# amp_soha_v3.net
KiCad netlist of a schematic drawn in EAGLE
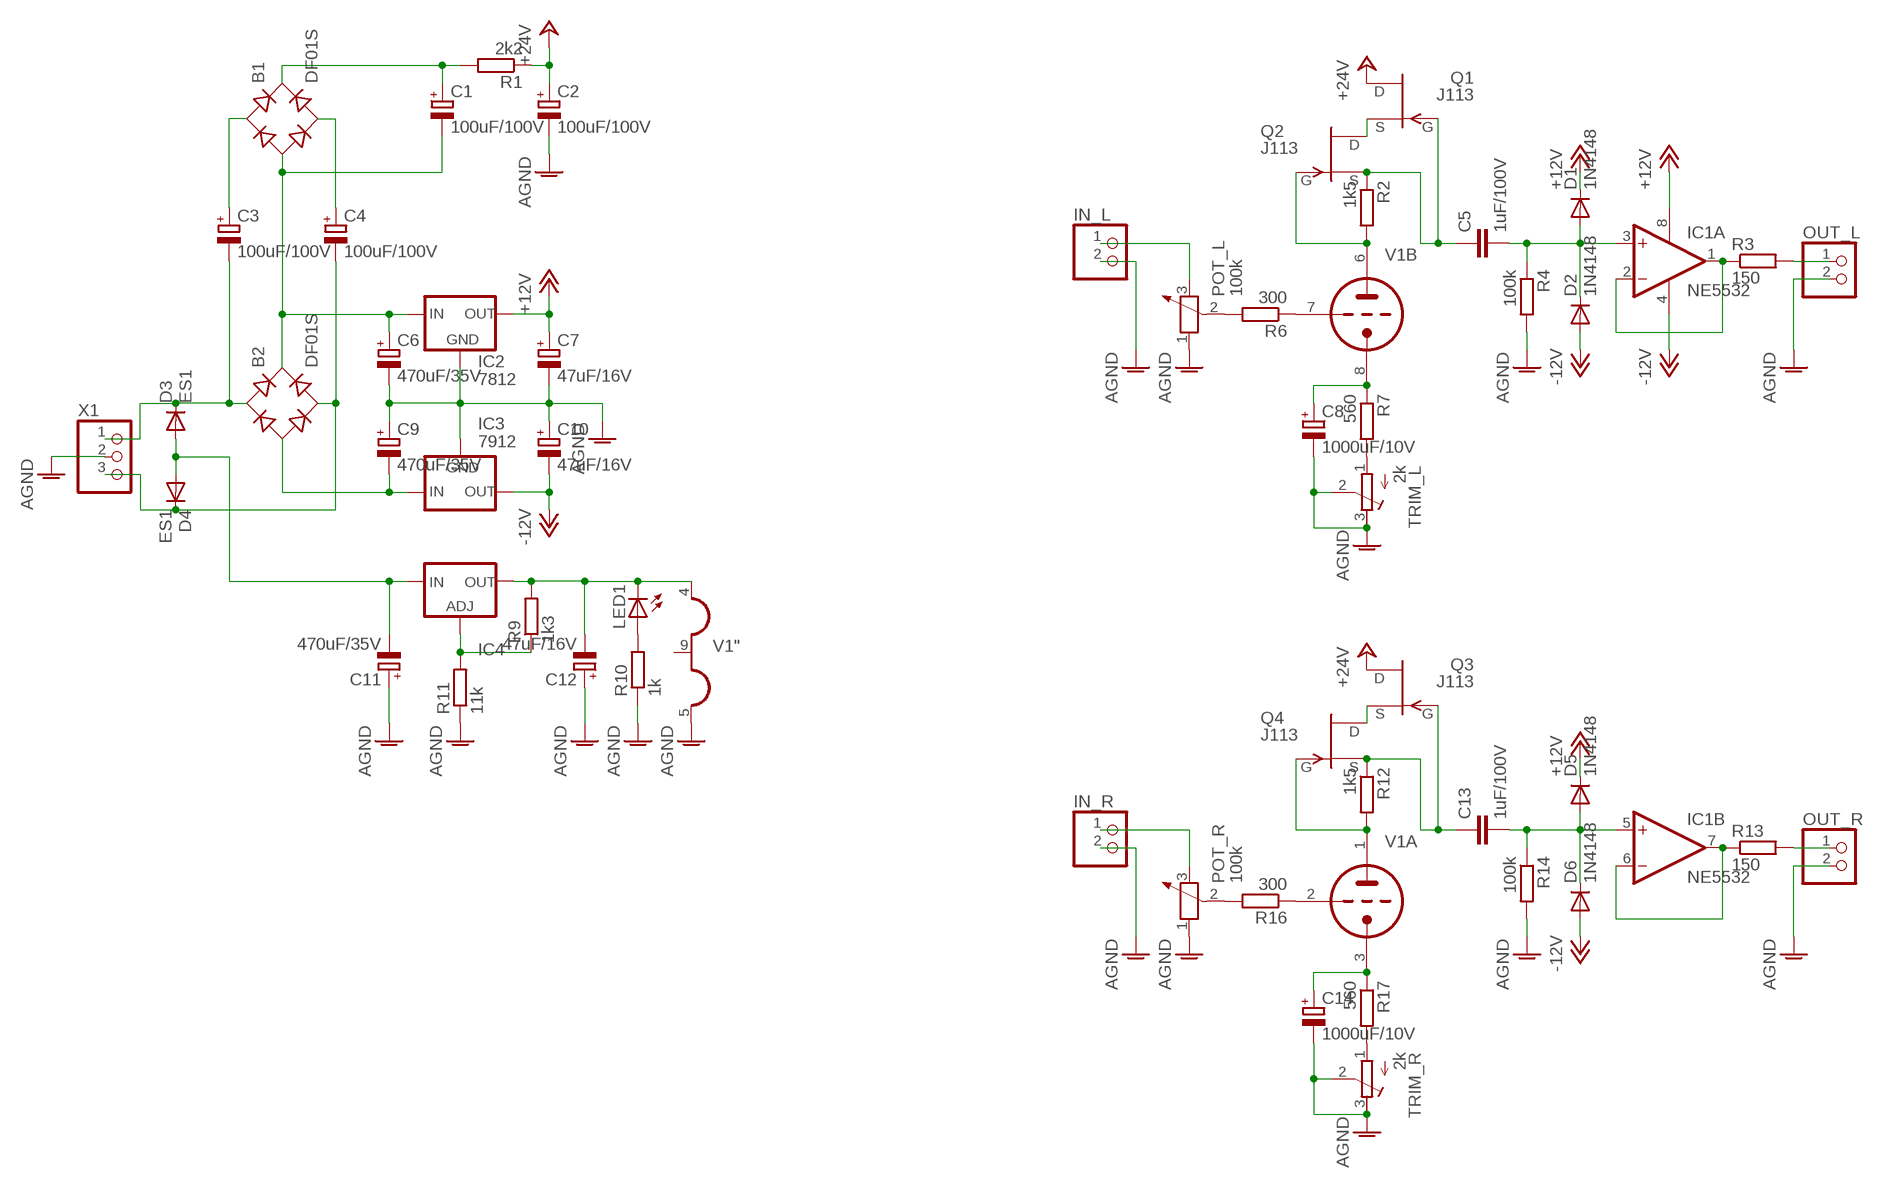
[diagram p0: schematic, sheet 1]

(export (version "E")
  (design (tool "Eeschema 10.0.6"))
  (components
    (comp (ref "B1")
      (value "DF01S")
      (footprint "eagle-import:DFS")
      (libsource (lib "eagle-import") (part "DFS01"))
    )
    (comp (ref "B2")
      (value "DF01S")
      (footprint "eagle-import:DFS")
      (libsource (lib "eagle-import") (part "DFS01"))
    )
    (comp (ref "C1")
      (value "100uF/100V")
      (footprint "eagle-import:E5-10,5")
      (libsource (lib "eagle-import") (part "CPOL-EUE5-10,5"))
    )
    (comp (ref "C2")
      (value "100uF/100V")
      (footprint "eagle-import:E5-10,5")
      (libsource (lib "eagle-import") (part "CPOL-EUE5-10,5"))
    )
    (comp (ref "C3")
      (value "100uF/100V")
      (footprint "eagle-import:E5-10,5")
      (libsource (lib "eagle-import") (part "CPOL-EUE5-10,5"))
    )
    (comp (ref "C4")
      (value "100uF/100V")
      (footprint "eagle-import:E5-10,5")
      (libsource (lib "eagle-import") (part "CPOL-EUE5-10,5"))
    )
    (comp (ref "C5")
      (value "1uF/100V")
      (footprint "eagle-import:C075-052X106")
      (libsource (lib "eagle-import") (part "C-EU075-052X106"))
    )
    (comp (ref "C6")
      (value "470uF/35V")
      (footprint "eagle-import:E5-10,5")
      (libsource (lib "eagle-import") (part "CPOL-EUE5-10,5"))
    )
    (comp (ref "C7")
      (value "47uF/16V")
      (footprint "eagle-import:E2,5-6")
      (libsource (lib "eagle-import") (part "CPOL-EUE2.5-6"))
    )
    (comp (ref "C8")
      (value "1000uF/10V")
      (footprint "eagle-import:E5-10,5")
      (libsource (lib "eagle-import") (part "CPOL-EUE5-10,5"))
    )
    (comp (ref "C9")
      (value "470uF/35V")
      (footprint "eagle-import:E5-10,5")
      (libsource (lib "eagle-import") (part "CPOL-EUE5-10,5"))
    )
    (comp (ref "C10")
      (value "47uF/16V")
      (footprint "eagle-import:E2,5-6")
      (libsource (lib "eagle-import") (part "CPOL-EUE2.5-6"))
    )
    (comp (ref "C11")
      (value "470uF/35V")
      (footprint "eagle-import:E5-10,5")
      (libsource (lib "eagle-import") (part "CPOL-EUE5-10,5"))
    )
    (comp (ref "C12")
      (value "47uF/16V")
      (footprint "eagle-import:E2,5-6")
      (libsource (lib "eagle-import") (part "CPOL-EUE2.5-6"))
    )
    (comp (ref "C13")
      (value "1uF/100V")
      (footprint "eagle-import:C075-052X106")
      (libsource (lib "eagle-import") (part "C-EU075-052X106"))
    )
    (comp (ref "C14")
      (value "1000uF/10V")
      (footprint "eagle-import:E5-10,5")
      (libsource (lib "eagle-import") (part "CPOL-EUE5-10,5"))
    )
    (comp (ref "D1")
      (value "1N4148")
      (footprint "eagle-import:D0805")
      (libsource (lib "eagle-import") (part "1N4148"))
    )
    (comp (ref "D2")
      (value "1N4148")
      (footprint "eagle-import:D0805")
      (libsource (lib "eagle-import") (part "1N4148"))
    )
    (comp (ref "D3")
      (value "ES1")
      (footprint "eagle-import:DO-214AC")
      (libsource (lib "eagle-import") (part "ES1"))
    )
    (comp (ref "D4")
      (value "ES1")
      (footprint "eagle-import:DO-214AC")
      (libsource (lib "eagle-import") (part "ES1"))
    )
    (comp (ref "D5")
      (value "1N4148")
      (footprint "eagle-import:D0805")
      (libsource (lib "eagle-import") (part "1N4148"))
    )
    (comp (ref "D6")
      (value "1N4148")
      (footprint "eagle-import:D0805")
      (libsource (lib "eagle-import") (part "1N4148"))
    )
    (comp (ref "IC1")
      (value "NE5532")
      (footprint "eagle-import:SO08")
      (libsource (lib "eagle-import") (part "NE5535U"))
    )
    (comp (ref "IC2")
      (value "7812")
      (footprint "eagle-import:78XXS")
      (libsource (lib "eagle-import") (part "78XXTO-220"))
    )
    (comp (ref "IC3")
      (value "7912")
      (footprint "eagle-import:79XXS")
      (libsource (lib "eagle-import") (part "79XXTO-220"))
    )
    (comp (ref "IC4")
      (value "LM337TS")
      (footprint "eagle-import:337TS")
      (libsource (lib "eagle-import") (part "LM337TS"))
    )
    (comp (ref "IN_L")
      (value "PINHD-1X2")
      (footprint "eagle-import:1X02")
      (libsource (lib "eagle-import") (part "PINHD-1X2"))
    )
    (comp (ref "IN_R")
      (value "PINHD-1X2")
      (footprint "eagle-import:1X02")
      (libsource (lib "eagle-import") (part "PINHD-1X2"))
    )
    (comp (ref "LED1")
      (value "LED5MM")
      (footprint "eagle-import:LED5MM")
      (libsource (lib "eagle-import") (part "LED5MM"))
    )
    (comp (ref "OUT_L")
      (value "PINHD-1X2")
      (footprint "eagle-import:1X02")
      (libsource (lib "eagle-import") (part "PINHD-1X2"))
    )
    (comp (ref "OUT_R")
      (value "PINHD-1X2")
      (footprint "eagle-import:1X02")
      (libsource (lib "eagle-import") (part "PINHD-1X2"))
    )
    (comp (ref "POT_L")
      (value "100k")
      (footprint "eagle-import:1X03")
      (libsource (lib "eagle-import") (part "POTENTIOMETER_"))
    )
    (comp (ref "POT_R")
      (value "100k")
      (footprint "eagle-import:1X03")
      (libsource (lib "eagle-import") (part "POTENTIOMETER_"))
    )
    (comp (ref "Q1")
      (value "J113")
      (footprint "eagle-import:TO92")
      (libsource (lib "eagle-import") (part "J113"))
    )
    (comp (ref "Q2")
      (value "J113")
      (footprint "eagle-import:TO92")
      (libsource (lib "eagle-import") (part "J113"))
    )
    (comp (ref "Q3")
      (value "J113")
      (footprint "eagle-import:TO92")
      (libsource (lib "eagle-import") (part "J113"))
    )
    (comp (ref "Q4")
      (value "J113")
      (footprint "eagle-import:TO92")
      (libsource (lib "eagle-import") (part "J113"))
    )
    (comp (ref "R1")
      (value "2k2")
      (footprint "eagle-import:R0805")
      (libsource (lib "eagle-import") (part "R-EU_"))
    )
    (comp (ref "R2")
      (value "1k5")
      (footprint "eagle-import:R0805")
      (libsource (lib "eagle-import") (part "R-EU_"))
    )
    (comp (ref "R3")
      (value "150")
      (footprint "eagle-import:R0805")
      (libsource (lib "eagle-import") (part "R-EU_"))
    )
    (comp (ref "R4")
      (value "100k")
      (footprint "eagle-import:R0805")
      (libsource (lib "eagle-import") (part "R-EU_"))
    )
    (comp (ref "R6")
      (value "300")
      (footprint "eagle-import:R0805")
      (libsource (lib "eagle-import") (part "R-EU_"))
    )
    (comp (ref "R7")
      (value "560")
      (footprint "eagle-import:R0805")
      (libsource (lib "eagle-import") (part "R-EU_"))
    )
    (comp (ref "R9")
      (value "1k3")
      (footprint "eagle-import:R0805")
      (libsource (lib "eagle-import") (part "R-EU_"))
    )
    (comp (ref "R10")
      (value "1k")
      (footprint "eagle-import:R0805")
      (libsource (lib "eagle-import") (part "R-EU_"))
    )
    (comp (ref "R11")
      (value "11k")
      (footprint "eagle-import:R0805")
      (libsource (lib "eagle-import") (part "R-EU_"))
    )
    (comp (ref "R12")
      (value "1k5")
      (footprint "eagle-import:R0805")
      (libsource (lib "eagle-import") (part "R-EU_"))
    )
    (comp (ref "R13")
      (value "150")
      (footprint "eagle-import:R0805")
      (libsource (lib "eagle-import") (part "R-EU_"))
    )
    (comp (ref "R14")
      (value "100k")
      (footprint "eagle-import:R0805")
      (libsource (lib "eagle-import") (part "R-EU_"))
    )
    (comp (ref "R16")
      (value "300")
      (footprint "eagle-import:R0805")
      (libsource (lib "eagle-import") (part "R-EU_"))
    )
    (comp (ref "R17")
      (value "560")
      (footprint "eagle-import:R0805")
      (libsource (lib "eagle-import") (part "R-EU_"))
    )
    (comp (ref "TRIM_L")
      (value "2k")
      (footprint "eagle-import:RTRIM3296W")
      (libsource (lib "eagle-import") (part "RTRIM329W"))
    )
    (comp (ref "TRIM_R")
      (value "2k")
      (footprint "eagle-import:RTRIM3296W")
      (libsource (lib "eagle-import") (part "RTRIM329W"))
    )
    (comp (ref "V1")
      (value "12AU7-P")
      (footprint "eagle-import:NOVAL")
      (libsource (lib "eagle-import") (part "12AU7-P"))
    )
    (comp (ref "X1")
      (value "W237-103")
      (footprint "eagle-import:W237-103")
      (libsource (lib "eagle-import") (part "W237-103"))
    )
  )
  (nets
    (net (code "1") (name "+12V") (class "Default")
      (node (ref "C7") (pin "+") (pinfunction "+_+") (pintype "passive"))
      (node (ref "D1") (pin "K") (pinfunction "C_K") (pintype "passive"))
      (node (ref "D5") (pin "K") (pinfunction "C_K") (pintype "passive"))
      (node (ref "IC1") (pin "8") (pinfunction "V+_8") (pintype "power_in"))
      (node (ref "IC2") (pin "OUT") (pinfunction "OUT_OUT") (pintype "passive"))
    )
    (net (code "2") (name "+24V") (class "Default")
      (node (ref "C2") (pin "+") (pinfunction "+_+") (pintype "passive"))
      (node (ref "Q1") (pin "3") (pinfunction "D_3") (pintype "passive"))
      (node (ref "Q3") (pin "3") (pinfunction "D_3") (pintype "passive"))
      (node (ref "R1") (pin "1") (pinfunction "1_1") (pintype "passive"))
    )
    (net (code "3") (name "-12V") (class "Default")
      (node (ref "C10") (pin "-") (pinfunction "-_-") (pintype "passive"))
      (node (ref "D2") (pin "A") (pinfunction "A_A") (pintype "passive"))
      (node (ref "D6") (pin "A") (pinfunction "A_A") (pintype "passive"))
      (node (ref "IC1") (pin "4") (pinfunction "V-_4") (pintype "power_in"))
      (node (ref "IC3") (pin "OUT") (pinfunction "OUT_OUT") (pintype "passive"))
    )
    (net (code "4") (name "AGND") (class "Default")
      (node (ref "C10") (pin "+") (pinfunction "+_+") (pintype "passive"))
      (node (ref "C11") (pin "+") (pinfunction "+_+") (pintype "passive"))
      (node (ref "C12") (pin "+") (pinfunction "+_+") (pintype "passive"))
      (node (ref "C14") (pin "-") (pinfunction "-_-") (pintype "passive"))
      (node (ref "C2") (pin "-") (pinfunction "-_-") (pintype "passive"))
      (node (ref "C6") (pin "-") (pinfunction "-_-") (pintype "passive"))
      (node (ref "C7") (pin "-") (pinfunction "-_-") (pintype "passive"))
      (node (ref "C8") (pin "-") (pinfunction "-_-") (pintype "passive"))
      (node (ref "C9") (pin "+") (pinfunction "+_+") (pintype "passive"))
      (node (ref "IC2") (pin "GND") (pinfunction "GND_GND") (pintype "input"))
      (node (ref "IC3") (pin "GND") (pinfunction "GND_GND") (pintype "input"))
      (node (ref "IN_L") (pin "2") (pinfunction "2_2") (pintype "passive"))
      (node (ref "IN_R") (pin "2") (pinfunction "2_2") (pintype "passive"))
      (node (ref "OUT_L") (pin "2") (pinfunction "2_2") (pintype "passive"))
      (node (ref "OUT_R") (pin "2") (pinfunction "2_2") (pintype "passive"))
      (node (ref "POT_L") (pin "1") (pinfunction "1_1") (pintype "passive"))
      (node (ref "POT_R") (pin "1") (pinfunction "1_1") (pintype "passive"))
      (node (ref "R10") (pin "1") (pinfunction "1_1") (pintype "passive"))
      (node (ref "R11") (pin "1") (pinfunction "1_1") (pintype "passive"))
      (node (ref "R14") (pin "2") (pinfunction "2_2") (pintype "passive"))
      (node (ref "R4") (pin "2") (pinfunction "2_2") (pintype "passive"))
      (node (ref "TRIM_L") (pin "2") (pinfunction "S_2") (pintype "passive"))
      (node (ref "TRIM_L") (pin "3") (pinfunction "E_3") (pintype "passive"))
      (node (ref "TRIM_R") (pin "2") (pinfunction "S_2") (pintype "passive"))
      (node (ref "TRIM_R") (pin "3") (pinfunction "E_3") (pintype "passive"))
      (node (ref "V1") (pin "5") (pinfunction "H3_5") (pintype "passive"))
      (node (ref "X1") (pin "2") (pinfunction "2_2") (pintype "passive"))
    )
    (net (code "5") (name "Net-(B1-Pad+)") (class "Default")
      (node (ref "B1") (pin "+") (pinfunction "+_+") (pintype "passive"))
      (node (ref "C1") (pin "+") (pinfunction "+_+") (pintype "passive"))
      (node (ref "R1") (pin "2") (pinfunction "2_2") (pintype "passive"))
    )
    (net (code "6") (name "Net-(B1-Pad-)") (class "Default")
      (node (ref "B1") (pin "-") (pinfunction "-_-") (pintype "passive"))
      (node (ref "B2") (pin "+") (pinfunction "+_+") (pintype "passive"))
      (node (ref "C1") (pin "-") (pinfunction "-_-") (pintype "passive"))
      (node (ref "C6") (pin "+") (pinfunction "+_+") (pintype "passive"))
      (node (ref "IC2") (pin "IN") (pinfunction "IN_IN") (pintype "input"))
    )
    (net (code "7") (name "Net-(B1-PadAC1)") (class "Default")
      (node (ref "B1") (pin "AC1") (pinfunction "AC1_AC1") (pintype "passive"))
      (node (ref "C3") (pin "+") (pinfunction "+_+") (pintype "passive"))
    )
    (net (code "8") (name "Net-(B1-PadAC2)") (class "Default")
      (node (ref "B1") (pin "AC2") (pinfunction "AC2_AC2") (pintype "passive"))
      (node (ref "C4") (pin "+") (pinfunction "+_+") (pintype "passive"))
    )
    (net (code "9") (name "Net-(B2-Pad-)") (class "Default")
      (node (ref "B2") (pin "-") (pinfunction "-_-") (pintype "passive"))
      (node (ref "C9") (pin "-") (pinfunction "-_-") (pintype "passive"))
      (node (ref "IC3") (pin "IN") (pinfunction "IN_IN") (pintype "input"))
    )
    (net (code "10") (name "Net-(B2-PadAC1)") (class "Default")
      (node (ref "B2") (pin "AC1") (pinfunction "AC1_AC1") (pintype "passive"))
      (node (ref "C3") (pin "-") (pinfunction "-_-") (pintype "passive"))
      (node (ref "D3") (pin "C") (pinfunction "C_C") (pintype "passive"))
      (node (ref "X1") (pin "1") (pinfunction "1_1") (pintype "passive"))
    )
    (net (code "11") (name "Net-(B2-PadAC2)") (class "Default")
      (node (ref "B2") (pin "AC2") (pinfunction "AC2_AC2") (pintype "passive"))
      (node (ref "C4") (pin "-") (pinfunction "-_-") (pintype "passive"))
      (node (ref "D4") (pin "C") (pinfunction "C_C") (pintype "passive"))
      (node (ref "X1") (pin "3") (pinfunction "3_3") (pintype "passive"))
    )
    (net (code "12") (name "Net-(D2-C)") (class "Default")
      (node (ref "C5") (pin "2") (pinfunction "2_2") (pintype "passive"))
      (node (ref "D1") (pin "A") (pinfunction "A_A") (pintype "passive"))
      (node (ref "D2") (pin "K") (pinfunction "C_K") (pintype "passive"))
      (node (ref "IC1") (pin "3") (pinfunction "+IN_3") (pintype "input"))
      (node (ref "R4") (pin "1") (pinfunction "1_1") (pintype "passive"))
    )
    (net (code "13") (name "Net-(D6-C)") (class "Default")
      (node (ref "C13") (pin "2") (pinfunction "2_2") (pintype "passive"))
      (node (ref "D5") (pin "A") (pinfunction "A_A") (pintype "passive"))
      (node (ref "D6") (pin "K") (pinfunction "C_K") (pintype "passive"))
      (node (ref "IC1") (pin "5") (pinfunction "+IN_5") (pintype "input"))
      (node (ref "R14") (pin "1") (pinfunction "1_1") (pintype "passive"))
    )
    (net (code "14") (name "Net-(IC1A--IN)") (class "Default")
      (node (ref "IC1") (pin "1") (pinfunction "OUT_1") (pintype "output"))
      (node (ref "IC1") (pin "2") (pinfunction "-IN_2") (pintype "input"))
      (node (ref "R3") (pin "1") (pinfunction "1_1") (pintype "passive"))
    )
    (net (code "15") (name "Net-(IC1B--IN)") (class "Default")
      (node (ref "IC1") (pin "6") (pinfunction "-IN_6") (pintype "input"))
      (node (ref "IC1") (pin "7") (pinfunction "OUT_7") (pintype "output"))
      (node (ref "R13") (pin "1") (pinfunction "1_1") (pintype "passive"))
    )
    (net (code "16") (name "Net-(IC4-ADJ)") (class "Default")
      (node (ref "IC4") (pin "1") (pinfunction "ADJ_1") (pintype "input"))
      (node (ref "R11") (pin "2") (pinfunction "2_2") (pintype "passive"))
      (node (ref "R9") (pin "1") (pinfunction "1_1") (pintype "passive"))
    )
    (net (code "17") (name "Net-(IC4-IN)") (class "Default")
      (node (ref "C11") (pin "-") (pinfunction "-_-") (pintype "passive"))
      (node (ref "D3") (pin "A") (pinfunction "A_A") (pintype "passive"))
      (node (ref "D4") (pin "A") (pinfunction "A_A") (pintype "passive"))
      (node (ref "IC4") (pin "2") (pinfunction "IN_2") (pintype "input"))
    )
    (net (code "18") (name "Net-(IC4-OUT)") (class "Default")
      (node (ref "C12") (pin "-") (pinfunction "-_-") (pintype "passive"))
      (node (ref "IC4") (pin "3") (pinfunction "OUT_3") (pintype "passive"))
      (node (ref "LED1") (pin "K") (pinfunction "C_K") (pintype "passive"))
      (node (ref "R9") (pin "2") (pinfunction "2_2") (pintype "passive"))
      (node (ref "V1") (pin "4") (pinfunction "H1_4") (pintype "passive"))
    )
    (net (code "19") (name "Net-(LED1-PadA)") (class "Default")
      (node (ref "LED1") (pin "A") (pinfunction "A_A") (pintype "passive"))
      (node (ref "R10") (pin "2") (pinfunction "2_2") (pintype "passive"))
    )
    (net (code "20") (name "Net-(OUT_L-Pad1)") (class "Default")
      (node (ref "OUT_L") (pin "1") (pinfunction "1_1") (pintype "passive"))
      (node (ref "R3") (pin "2") (pinfunction "2_2") (pintype "passive"))
    )
    (net (code "21") (name "Net-(OUT_R-Pad1)") (class "Default")
      (node (ref "OUT_R") (pin "1") (pinfunction "1_1") (pintype "passive"))
      (node (ref "R13") (pin "2") (pinfunction "2_2") (pintype "passive"))
    )
    (net (code "22") (name "Net-(POT_L-2)") (class "Default")
      (node (ref "IN_L") (pin "1") (pinfunction "1_1") (pintype "passive"))
      (node (ref "POT_L") (pin "3") (pinfunction "2_3") (pintype "passive"))
    )
    (net (code "23") (name "Net-(POT_L-3)") (class "Default")
      (node (ref "POT_L") (pin "2") (pinfunction "3_2") (pintype "passive"))
      (node (ref "R6") (pin "2") (pinfunction "2_2") (pintype "passive"))
    )
    (net (code "24") (name "Net-(POT_R-2)") (class "Default")
      (node (ref "IN_R") (pin "1") (pinfunction "1_1") (pintype "passive"))
      (node (ref "POT_R") (pin "3") (pinfunction "2_3") (pintype "passive"))
    )
    (net (code "25") (name "Net-(POT_R-3)") (class "Default")
      (node (ref "POT_R") (pin "2") (pinfunction "3_2") (pintype "passive"))
      (node (ref "R16") (pin "2") (pinfunction "2_2") (pintype "passive"))
    )
    (net (code "26") (name "Net-(Q1-G)") (class "Default")
      (node (ref "C5") (pin "1") (pinfunction "1_1") (pintype "passive"))
      (node (ref "Q1") (pin "1") (pinfunction "G_1") (pintype "passive"))
      (node (ref "Q2") (pin "2") (pinfunction "S_2") (pintype "passive"))
      (node (ref "R2") (pin "1") (pinfunction "1_1") (pintype "passive"))
    )
    (net (code "27") (name "Net-(Q1-S)") (class "Default")
      (node (ref "Q1") (pin "2") (pinfunction "S_2") (pintype "passive"))
      (node (ref "Q2") (pin "3") (pinfunction "D_3") (pintype "passive"))
    )
    (net (code "28") (name "Net-(Q2-G)") (class "Default")
      (node (ref "Q2") (pin "1") (pinfunction "G_1") (pintype "passive"))
      (node (ref "R2") (pin "2") (pinfunction "2_2") (pintype "passive"))
      (node (ref "V1") (pin "6") (pinfunction "TA_6") (pintype "passive"))
    )
    (net (code "29") (name "Net-(Q3-G)") (class "Default")
      (node (ref "C13") (pin "1") (pinfunction "1_1") (pintype "passive"))
      (node (ref "Q3") (pin "1") (pinfunction "G_1") (pintype "passive"))
      (node (ref "Q4") (pin "2") (pinfunction "S_2") (pintype "passive"))
      (node (ref "R12") (pin "1") (pinfunction "1_1") (pintype "passive"))
    )
    (net (code "30") (name "Net-(Q3-S)") (class "Default")
      (node (ref "Q3") (pin "2") (pinfunction "S_2") (pintype "passive"))
      (node (ref "Q4") (pin "3") (pinfunction "D_3") (pintype "passive"))
    )
    (net (code "31") (name "Net-(Q4-G)") (class "Default")
      (node (ref "Q4") (pin "1") (pinfunction "G_1") (pintype "passive"))
      (node (ref "R12") (pin "2") (pinfunction "2_2") (pintype "passive"))
      (node (ref "V1") (pin "1") (pinfunction "TA_1") (pintype "passive"))
    )
    (net (code "32") (name "Net-(TRIM_L-A)") (class "Default")
      (node (ref "R7") (pin "2") (pinfunction "2_2") (pintype "passive"))
      (node (ref "TRIM_L") (pin "1") (pinfunction "A_1") (pintype "passive"))
    )
    (net (code "33") (name "Net-(TRIM_R-A)") (class "Default")
      (node (ref "R17") (pin "2") (pinfunction "2_2") (pintype "passive"))
      (node (ref "TRIM_R") (pin "1") (pinfunction "A_1") (pintype "passive"))
    )
    (net (code "34") (name "Net-(V1B-TG)") (class "Default")
      (node (ref "R16") (pin "1") (pinfunction "1_1") (pintype "passive"))
      (node (ref "V1") (pin "2") (pinfunction "TG_2") (pintype "passive"))
    )
    (net (code "35") (name "Net-(V1B-TK)") (class "Default")
      (node (ref "C14") (pin "+") (pinfunction "+_+") (pintype "passive"))
      (node (ref "R17") (pin "1") (pinfunction "1_1") (pintype "passive"))
      (node (ref "V1") (pin "3") (pinfunction "TK_3") (pintype "passive"))
    )
    (net (code "36") (name "Net-(V1C-TG)") (class "Default")
      (node (ref "R6") (pin "1") (pinfunction "1_1") (pintype "passive"))
      (node (ref "V1") (pin "7") (pinfunction "TG_7") (pintype "passive"))
    )
    (net (code "37") (name "Net-(V1C-TK)") (class "Default")
      (node (ref "C8") (pin "+") (pinfunction "+_+") (pintype "passive"))
      (node (ref "R7") (pin "1") (pinfunction "1_1") (pintype "passive"))
      (node (ref "V1") (pin "8") (pinfunction "TK_8") (pintype "passive"))
    )
    (net (code "38") (name "unconnected-(V1A-H2-Pad9)") (class "Default")
      (node (ref "V1") (pin "9") (pinfunction "H2_9") (pintype "passive"))
    )
  )
)
